# SparkFun_LoRaSerial_433MHz_-_1W.net
KiCad netlist of a schematic drawn in EAGLE
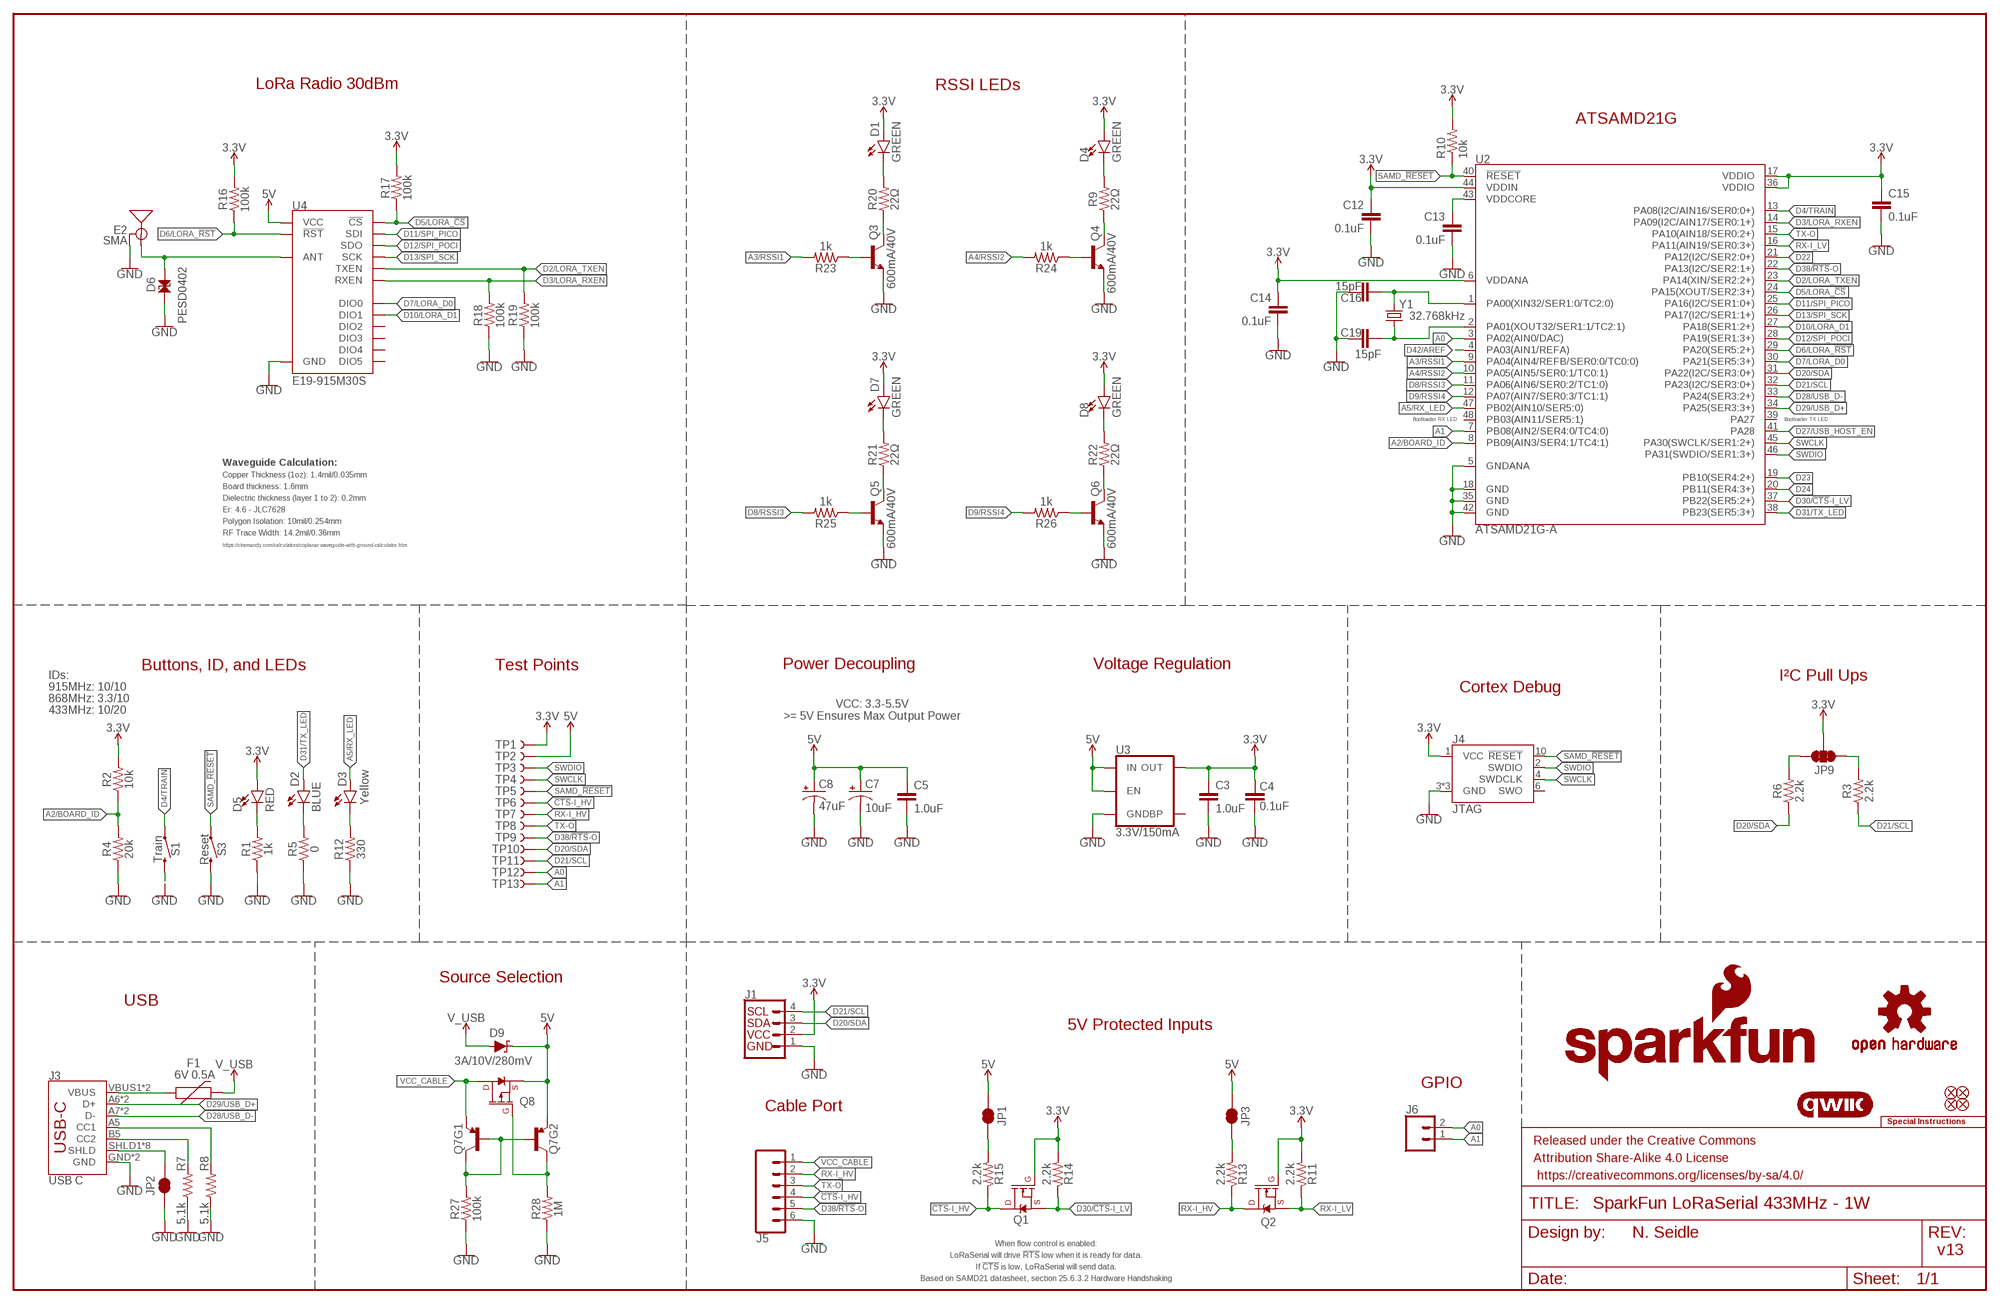
[diagram p0: schematic, sheet 1]

(export (version "E")
  (design (tool "Eeschema 10.0.6"))
  (components
    (comp (ref "C3")
      (value "1.0uF")
      (footprint "eagle-import:0603")
      (libsource (lib "eagle-import") (part "1.0UF-0603-16V-10%-X7R"))
    )
    (comp (ref "C4")
      (value "0.1uF")
      (footprint "eagle-import:0603")
      (libsource (lib "eagle-import") (part "0.1UF-0603-25V-5%"))
    )
    (comp (ref "C5")
      (value "1.0uF")
      (footprint "eagle-import:0603")
      (libsource (lib "eagle-import") (part "1.0UF-0603-16V-10%-X7R"))
    )
    (comp (ref "C7")
      (value "10uF")
      (footprint "eagle-import:EIA3216")
      (libsource (lib "eagle-import") (part "10UF-POLAR-EIA3216-16V-10%(TANT)"))
    )
    (comp (ref "C8")
      (value "47uF")
      (footprint "eagle-import:EIA3528")
      (libsource (lib "eagle-import") (part "47UF-POLAR-EIA3528-10V-10%"))
    )
    (comp (ref "C12")
      (value "0.1uF")
      (footprint "eagle-import:0603")
      (libsource (lib "eagle-import") (part "0.1UF-0603-25V-(+80/-20%)"))
    )
    (comp (ref "C13")
      (value "0.1uF")
      (footprint "eagle-import:0603")
      (libsource (lib "eagle-import") (part "0.1UF-0603-25V-(+80/-20%)"))
    )
    (comp (ref "C14")
      (value "0.1uF")
      (footprint "eagle-import:0603")
      (libsource (lib "eagle-import") (part "0.1UF-0603-25V-(+80/-20%)"))
    )
    (comp (ref "C15")
      (value "0.1uF")
      (footprint "eagle-import:0603")
      (libsource (lib "eagle-import") (part "0.1UF-0603-25V-(+80/-20%)"))
    )
    (comp (ref "C16")
      (value "15pF")
      (footprint "eagle-import:0603")
      (libsource (lib "eagle-import") (part "15PF-0603-50V-5%"))
    )
    (comp (ref "C19")
      (value "15pF")
      (footprint "eagle-import:0603")
      (libsource (lib "eagle-import") (part "15PF-0603-50V-5%"))
    )
    (comp (ref "D1")
      (value "GREEN")
      (footprint "eagle-import:LED-0603")
      (libsource (lib "eagle-import") (part "LED-GREEN0603"))
    )
    (comp (ref "D2")
      (value "BLUE")
      (footprint "eagle-import:LED-0603")
      (libsource (lib "eagle-import") (part "LED-BLUE0603"))
    )
    (comp (ref "D3")
      (value "Yellow")
      (footprint "eagle-import:LED-0603")
      (libsource (lib "eagle-import") (part "LED-YELLOW0603"))
    )
    (comp (ref "D4")
      (value "GREEN")
      (footprint "eagle-import:LED-0603")
      (libsource (lib "eagle-import") (part "LED-GREEN0603"))
    )
    (comp (ref "D5")
      (value "RED")
      (footprint "eagle-import:LED-0603")
      (libsource (lib "eagle-import") (part "LED-RED0603"))
    )
    (comp (ref "D6")
      (value "PESD0402")
      (footprint "eagle-import:0402-TIGHT")
      (libsource (lib "eagle-import") (part "PESD0402-0402T"))
    )
    (comp (ref "D7")
      (value "GREEN")
      (footprint "eagle-import:LED-0603")
      (libsource (lib "eagle-import") (part "LED-GREEN0603"))
    )
    (comp (ref "D8")
      (value "GREEN")
      (footprint "eagle-import:LED-0603")
      (libsource (lib "eagle-import") (part "LED-GREEN0603"))
    )
    (comp (ref "D9")
      (value "3A/10V/280mV")
      (footprint "eagle-import:SOD-323")
      (libsource (lib "eagle-import") (part "DIODE-SCHOTTKY-BAT60A"))
    )
    (comp (ref "E2")
      (value "SMA")
      (footprint "eagle-import:SMA-EDGE")
      (libsource (lib "eagle-import") (part "ANTENNA-SMA-GROUNDEDEDGE_SMA"))
    )
    (comp (ref "F1")
      (value "6V 0.5A")
      (footprint "eagle-import:0805")
      (libsource (lib "eagle-import") (part "PPTC_6V500MA"))
    )
    (comp (ref "FID1")
      (value "FIDUCIAL1X2")
      (footprint "eagle-import:FIDUCIAL-1X2")
      (libsource (lib "eagle-import") (part "FIDUCIAL1X2"))
    )
    (comp (ref "FID2")
      (value "FIDUCIAL1X2")
      (footprint "eagle-import:FIDUCIAL-1X2")
      (libsource (lib "eagle-import") (part "FIDUCIAL1X2"))
    )
    (comp (ref "FID3")
      (value "FIDUCIAL1X2")
      (footprint "eagle-import:FIDUCIAL-1X2")
      (libsource (lib "eagle-import") (part "FIDUCIAL1X2"))
    )
    (comp (ref "FID4")
      (value "FIDUCIAL1X2")
      (footprint "eagle-import:FIDUCIAL-1X2")
      (libsource (lib "eagle-import") (part "FIDUCIAL1X2"))
    )
    (comp (ref "FRAME3")
      (value "FRAME-LEDGER")
      (footprint "eagle-import:CREATIVE_COMMONS")
      (libsource (lib "eagle-import") (part "FRAME-LEDGER"))
    )
    (comp (ref "J1")
      (value "QWIIC_RIGHT_ANGLE")
      (footprint "eagle-import:JST04_1MM_RA")
      (libsource (lib "eagle-import") (part "QWIIC_CONNECTORJS-1MM"))
    )
    (comp (ref "J3")
      (value "USB C")
      (footprint "eagle-import:USB-C-16P")
      (libsource (lib "eagle-import") (part "USB_C16PIN"))
    )
    (comp (ref "J4")
      (value "JTAG")
      (footprint "eagle-import:2X5-PTH-1.27MM-NO_SILK")
      (libsource (lib "eagle-import") (part "CORTEX_JTAG_DEBUG_MINIMUM_PTH_NS"))
    )
    (comp (ref "J5")
      (value "CONN_06JST-SMD-LOCKING")
      (footprint "eagle-import:JST-6-SMD-1.25MM-LOCKING")
      (libsource (lib "eagle-import") (part "CONN_06JST-SMD-LOCKING"))
    )
    (comp (ref "J6")
      (value "CONN_021X02_NO_SILK")
      (footprint "eagle-import:1X02_NO_SILK")
      (libsource (lib "eagle-import") (part "CONN_021X02_NO_SILK"))
    )
    (comp (ref "JP1")
      (value "JUMPER-SMT_2_NC_TRACE_SILK")
      (footprint "eagle-import:SMT-JUMPER_2_NC_TRACE_SILK")
      (libsource (lib "eagle-import") (part "JUMPER-SMT_2_NC_TRACE_SILK"))
    )
    (comp (ref "JP2")
      (value "JUMPER-SMT_2_NC_TRACE_SILK")
      (footprint "eagle-import:SMT-JUMPER_2_NC_TRACE_SILK")
      (libsource (lib "eagle-import") (part "JUMPER-SMT_2_NC_TRACE_SILK"))
    )
    (comp (ref "JP3")
      (value "JUMPER-SMT_2_NC_TRACE_SILK")
      (footprint "eagle-import:SMT-JUMPER_2_NC_TRACE_SILK")
      (libsource (lib "eagle-import") (part "JUMPER-SMT_2_NC_TRACE_SILK"))
    )
    (comp (ref "JP9")
      (value "JUMPER-SMT_3_2-NC_TRACE_SILK")
      (footprint "eagle-import:SMT-JUMPER_3_2-NC_TRACE_SILK")
      (libsource (lib "eagle-import") (part "JUMPER-SMT_3_2-NC_TRACE_SILK"))
    )
    (comp (ref "LOGO1")
      (value "SPECIAL_INSTRUCTIONS-ORDERING")
      (footprint "eagle-import:ORDERING_INSTRUCTIONS")
      (libsource (lib "eagle-import") (part "SPECIAL_INSTRUCTIONS-ORDERING"))
    )
    (comp (ref "LOGO2")
      (value "SFE_LOGO_NAME_FLAME9_MM")
      (footprint "eagle-import:SFE_LOGO_NAME_FLAME_9MM")
      (libsource (lib "eagle-import") (part "SFE_LOGO_NAME_FLAME9_MM"))
    )
    (comp (ref "LOGO3")
      (value "QWIIC_LOGO_CONNECTOR")
      (footprint "eagle-import:QWIIC_5.5MM")
      (libsource (lib "eagle-import") (part "QWIIC_LOGO_CONNECTOR"))
    )
    (comp (ref "LOGO4")
      (value "OSHW-LOGOMINI")
      (footprint "eagle-import:OSHW-LOGO-MINI")
      (libsource (lib "eagle-import") (part "OSHW-LOGOMINI"))
    )
    (comp (ref "LOGO5")
      (value "SFE_LOGO_NAME9_MM")
      (footprint "eagle-import:SFE_LOGO_NAME_9MM")
      (libsource (lib "eagle-import") (part "SFE_LOGO_NAME9_MM"))
    )
    (comp (ref "Q1")
      (value "20V/0.2A/8MHz/1.2Ω/1Vth")
      (footprint "eagle-import:SOT-416FL")
      (libsource (lib "eagle-import") (part "MOSFET-NCH-RE1C002UNTCL"))
    )
    (comp (ref "Q2")
      (value "20V/0.2A/8MHz/1.2Ω/1Vth")
      (footprint "eagle-import:SOT-416FL")
      (libsource (lib "eagle-import") (part "MOSFET-NCH-RE1C002UNTCL"))
    )
    (comp (ref "Q3")
      (value "600mA/40V")
      (footprint "eagle-import:SOT23-3")
      (libsource (lib "eagle-import") (part "TRANS_NPN-MMBT2222AL"))
    )
    (comp (ref "Q4")
      (value "600mA/40V")
      (footprint "eagle-import:SOT23-3")
      (libsource (lib "eagle-import") (part "TRANS_NPN-MMBT2222AL"))
    )
    (comp (ref "Q5")
      (value "600mA/40V")
      (footprint "eagle-import:SOT23-3")
      (libsource (lib "eagle-import") (part "TRANS_NPN-MMBT2222AL"))
    )
    (comp (ref "Q6")
      (value "600mA/40V")
      (footprint "eagle-import:SOT23-3")
      (libsource (lib "eagle-import") (part "TRANS_NPN-MMBT2222AL"))
    )
    (comp (ref "Q7")
      (value "TRANS_PNP_DUALSOT-363")
      (footprint "eagle-import:SOT363_PHILIPS")
      (libsource (lib "eagle-import") (part "TRANS_PNP_DUALSOT-363"))
    )
    (comp (ref "Q8")
      (value "20V/4.2A/52mΩ/1.4W")
      (footprint "eagle-import:SOT23-3")
      (libsource (lib "eagle-import") (part "MOSFET_PCH-DMG2305UX-7"))
    )
    (comp (ref "R1")
      (value "1k")
      (footprint "eagle-import:0603")
      (libsource (lib "eagle-import") (part "1KOHM-0603-1/10W-1%"))
    )
    (comp (ref "R2")
      (value "10k")
      (footprint "eagle-import:0603")
      (libsource (lib "eagle-import") (part "10KOHM-0603-1/10W-1%"))
    )
    (comp (ref "R3")
      (value "2.2k")
      (footprint "eagle-import:0603")
      (libsource (lib "eagle-import") (part "2.2KOHM-0603-1/10W-1%"))
    )
    (comp (ref "R4")
      (value "20k")
      (footprint "eagle-import:0603")
      (libsource (lib "eagle-import") (part "20KOHM-0603-1/10W-1%"))
    )
    (comp (ref "R5")
      (value "0")
      (footprint "eagle-import:0603")
      (libsource (lib "eagle-import") (part "0OHM-0603-1/10W"))
    )
    (comp (ref "R6")
      (value "2.2k")
      (footprint "eagle-import:0603")
      (libsource (lib "eagle-import") (part "2.2KOHM-0603-1/10W-1%"))
    )
    (comp (ref "R7")
      (value "5.1k")
      (footprint "eagle-import:0603")
      (libsource (lib "eagle-import") (part "5.1KOHM5.1KOHM-0603-1/10W-1%"))
    )
    (comp (ref "R8")
      (value "5.1k")
      (footprint "eagle-import:0603")
      (libsource (lib "eagle-import") (part "5.1KOHM5.1KOHM-0603-1/10W-1%"))
    )
    (comp (ref "R9")
      (value "22Ω")
      (footprint "eagle-import:0603")
      (libsource (lib "eagle-import") (part "22OHM-0603-1/10W-1%"))
    )
    (comp (ref "R10")
      (value "10k")
      (footprint "eagle-import:0603")
      (libsource (lib "eagle-import") (part "10KOHM-0603-1/10W-1%"))
    )
    (comp (ref "R11")
      (value "2.2k")
      (footprint "eagle-import:0603")
      (libsource (lib "eagle-import") (part "2.2KOHM-0603-1/10W-1%"))
    )
    (comp (ref "R12")
      (value "330")
      (footprint "eagle-import:0603")
      (libsource (lib "eagle-import") (part "330OHM-0603-1/10W-1%"))
    )
    (comp (ref "R13")
      (value "2.2k")
      (footprint "eagle-import:0603")
      (libsource (lib "eagle-import") (part "2.2KOHM-0603-1/10W-1%"))
    )
    (comp (ref "R14")
      (value "2.2k")
      (footprint "eagle-import:0603")
      (libsource (lib "eagle-import") (part "2.2KOHM-0603-1/10W-1%"))
    )
    (comp (ref "R15")
      (value "2.2k")
      (footprint "eagle-import:0603")
      (libsource (lib "eagle-import") (part "2.2KOHM-0603-1/10W-1%"))
    )
    (comp (ref "R16")
      (value "100k")
      (footprint "eagle-import:0603")
      (libsource (lib "eagle-import") (part "100KOHM-0603-1/10W-1%"))
    )
    (comp (ref "R17")
      (value "100k")
      (footprint "eagle-import:0603")
      (libsource (lib "eagle-import") (part "100KOHM-0603-1/10W-1%"))
    )
    (comp (ref "R18")
      (value "100k")
      (footprint "eagle-import:0603")
      (libsource (lib "eagle-import") (part "100KOHM-0603-1/10W-1%"))
    )
    (comp (ref "R19")
      (value "100k")
      (footprint "eagle-import:0603")
      (libsource (lib "eagle-import") (part "100KOHM-0603-1/10W-1%"))
    )
    (comp (ref "R20")
      (value "22Ω")
      (footprint "eagle-import:0603")
      (libsource (lib "eagle-import") (part "22OHM-0603-1/10W-1%"))
    )
    (comp (ref "R21")
      (value "22Ω")
      (footprint "eagle-import:0603")
      (libsource (lib "eagle-import") (part "22OHM-0603-1/10W-1%"))
    )
    (comp (ref "R22")
      (value "22Ω")
      (footprint "eagle-import:0603")
      (libsource (lib "eagle-import") (part "22OHM-0603-1/10W-1%"))
    )
    (comp (ref "R23")
      (value "1k")
      (footprint "eagle-import:0603")
      (libsource (lib "eagle-import") (part "1KOHM-0603-1/10W-1%"))
    )
    (comp (ref "R24")
      (value "1k")
      (footprint "eagle-import:0603")
      (libsource (lib "eagle-import") (part "1KOHM-0603-1/10W-1%"))
    )
    (comp (ref "R25")
      (value "1k")
      (footprint "eagle-import:0603")
      (libsource (lib "eagle-import") (part "1KOHM-0603-1/10W-1%"))
    )
    (comp (ref "R26")
      (value "1k")
      (footprint "eagle-import:0603")
      (libsource (lib "eagle-import") (part "1KOHM-0603-1/10W-1%"))
    )
    (comp (ref "R27")
      (value "100k")
      (footprint "eagle-import:0603")
      (libsource (lib "eagle-import") (part "100KOHM-0603-1/10W-1%"))
    )
    (comp (ref "R28")
      (value "1M")
      (footprint "eagle-import:0603")
      (libsource (lib "eagle-import") (part "1MOHM-0603-1/4W-5%"))
    )
    (comp (ref "S1")
      (value "Train")
      (footprint "eagle-import:TACTILE_SWITCH_SMD_RIGHT_ANGLE")
      (libsource (lib "eagle-import") (part "MOMENTARY-SWITCH-SPST-SMD-RIGHT-ANGLE"))
    )
    (comp (ref "S3")
      (value "Reset")
      (footprint "eagle-import:TACTILE_SWITCH_SMD_5.2MM")
      (libsource (lib "eagle-import") (part "MOMENTARY-SWITCH-SPST-SMD-5.2-TALL-REDUNDANT"))
    )
    (comp (ref "TP1")
      (value "TEST-POINT3X5")
      (footprint "eagle-import:PAD.03X.05")
      (libsource (lib "eagle-import") (part "TEST-POINT3X5"))
    )
    (comp (ref "TP2")
      (value "TEST-POINT3X5")
      (footprint "eagle-import:PAD.03X.05")
      (libsource (lib "eagle-import") (part "TEST-POINT3X5"))
    )
    (comp (ref "TP3")
      (value "TEST-POINT3X5")
      (footprint "eagle-import:PAD.03X.05")
      (libsource (lib "eagle-import") (part "TEST-POINT3X5"))
    )
    (comp (ref "TP4")
      (value "TEST-POINT3X5")
      (footprint "eagle-import:PAD.03X.05")
      (libsource (lib "eagle-import") (part "TEST-POINT3X5"))
    )
    (comp (ref "TP5")
      (value "TEST-POINT3X5")
      (footprint "eagle-import:PAD.03X.05")
      (libsource (lib "eagle-import") (part "TEST-POINT3X5"))
    )
    (comp (ref "TP6")
      (value "TEST-POINT3X5")
      (footprint "eagle-import:PAD.03X.05")
      (libsource (lib "eagle-import") (part "TEST-POINT3X5"))
    )
    (comp (ref "TP7")
      (value "TEST-POINT3X5")
      (footprint "eagle-import:PAD.03X.05")
      (libsource (lib "eagle-import") (part "TEST-POINT3X5"))
    )
    (comp (ref "TP8")
      (value "TEST-POINT3X5")
      (footprint "eagle-import:PAD.03X.05")
      (libsource (lib "eagle-import") (part "TEST-POINT3X5"))
    )
    (comp (ref "TP9")
      (value "TEST-POINT3X5")
      (footprint "eagle-import:PAD.03X.05")
      (libsource (lib "eagle-import") (part "TEST-POINT3X5"))
    )
    (comp (ref "TP10")
      (value "TEST-POINT3X5")
      (footprint "eagle-import:PAD.03X.05")
      (libsource (lib "eagle-import") (part "TEST-POINT3X5"))
    )
    (comp (ref "TP11")
      (value "TEST-POINT3X5")
      (footprint "eagle-import:PAD.03X.05")
      (libsource (lib "eagle-import") (part "TEST-POINT3X5"))
    )
    (comp (ref "TP12")
      (value "TEST-POINT3X5")
      (footprint "eagle-import:PAD.03X.05")
      (libsource (lib "eagle-import") (part "TEST-POINT3X5"))
    )
    (comp (ref "TP13")
      (value "TEST-POINT3X5")
      (footprint "eagle-import:PAD.03X.05")
      (libsource (lib "eagle-import") (part "TEST-POINT3X5"))
    )
    (comp (ref "U2")
      (value "ATSAMD21G-A")
      (footprint "eagle-import:TQFP-48")
      (libsource (lib "eagle-import") (part "ATSAMD21G-A"))
    )
    (comp (ref "U3")
      (value "3.3V/150mA")
      (footprint "eagle-import:SOT23-5")
      (libsource (lib "eagle-import") (part "V_REG_MIC52053.3V"))
    )
    (comp (ref "U4")
      (value "E19-915M30S")
      (footprint "eagle-import:E19-433M30S")
      (libsource (lib "eagle-import") (part "LORA-E19433MHZ"))
    )
    (comp (ref "Y1")
      (value "32.768kHz")
      (footprint "eagle-import:CRYSTAL-SMD-3.2X1.5MM")
      (libsource (lib "eagle-import") (part "CRYSTAL3.2X1.5MM"))
    )
  )
  (nets
    (net (code "1") (name "/D5{slash}LORA_~{CS}") (class "Default")
      (node (ref "R17") (pin "1") (pinfunction "1_1") (pintype "passive"))
      (node (ref "U2") (pin "24") (pinfunction "PA15(XOUT/SER2:3+)_24") (pintype "bidirectional"))
      (node (ref "U4") (pin "15") (pinfunction "~{CS}_15") (pintype "bidirectional"))
    )
    (net (code "2") (name "/D6{slash}LORA_~{RST}") (class "Default")
      (node (ref "R16") (pin "1") (pinfunction "1_1") (pintype "passive"))
      (node (ref "U2") (pin "29") (pinfunction "PA20(SER5:2+)_29") (pintype "bidirectional"))
      (node (ref "U4") (pin "8") (pinfunction "~{RST}_8") (pintype "bidirectional"))
    )
    (net (code "3") (name "/D30{slash}~{CTS}-I_LV") (class "Default")
      (node (ref "Q1") (pin "2") (pinfunction "S_2") (pintype "bidirectional"))
      (node (ref "R14") (pin "1") (pinfunction "1_1") (pintype "passive"))
      (node (ref "U2") (pin "37") (pinfunction "PB22(SER5:2+)_37") (pintype "bidirectional"))
    )
    (net (code "4") (name "/D38{slash}~{RTS}-O") (class "Default")
      (node (ref "J5") (pin "5") (pinfunction "5_5") (pintype "passive"))
      (node (ref "TP9") (pin "1") (pinfunction "1_1") (pintype "bidirectional"))
      (node (ref "U2") (pin "22") (pinfunction "PA13(I2C/SER2:1+)_22") (pintype "bidirectional"))
    )
    (net (code "5") (name "/SAMD_~{RESET}") (class "Default")
      (node (ref "J4") (pin "10") (pinfunction "~{RESET}_10") (pintype "bidirectional"))
      (node (ref "R10") (pin "1") (pinfunction "1_1") (pintype "passive"))
      (node (ref "S3") (pin "1") (pinfunction "1_1") (pintype "passive"))
      (node (ref "S3") (pin "2") (pinfunction "1_2") (pintype "passive"))
      (node (ref "TP5") (pin "1") (pinfunction "1_1") (pintype "bidirectional"))
      (node (ref "U2") (pin "40") (pinfunction "~{RESET}_40") (pintype "bidirectional"))
    )
    (net (code "6") (name "/~{CTS}-I_HV") (class "Default")
      (node (ref "J5") (pin "4") (pinfunction "4_4") (pintype "passive"))
      (node (ref "Q1") (pin "3") (pinfunction "D_3") (pintype "bidirectional"))
      (node (ref "R15") (pin "1") (pinfunction "1_1") (pintype "passive"))
      (node (ref "TP6") (pin "1") (pinfunction "1_1") (pintype "bidirectional"))
    )
    (net (code "7") (name "3.3V") (class "Default")
      (node (ref "C12") (pin "1") (pinfunction "1_1") (pintype "passive"))
      (node (ref "C14") (pin "1") (pinfunction "1_1") (pintype "passive"))
      (node (ref "C15") (pin "1") (pinfunction "1_1") (pintype "passive"))
      (node (ref "C3") (pin "1") (pinfunction "1_1") (pintype "passive"))
      (node (ref "C4") (pin "2") (pinfunction "2_2") (pintype "passive"))
      (node (ref "D1") (pin "A") (pinfunction "A_A") (pintype "passive"))
      (node (ref "D4") (pin "A") (pinfunction "A_A") (pintype "passive"))
      (node (ref "D5") (pin "A") (pinfunction "A_A") (pintype "passive"))
      (node (ref "D7") (pin "A") (pinfunction "A_A") (pintype "passive"))
      (node (ref "D8") (pin "A") (pinfunction "A_A") (pintype "passive"))
      (node (ref "J1") (pin "2") (pinfunction "2_2") (pintype "power_in"))
      (node (ref "J4") (pin "1") (pinfunction "VCC_1") (pintype "bidirectional"))
      (node (ref "JP9") (pin "2") (pinfunction "2_2") (pintype "passive"))
      (node (ref "Q1") (pin "1") (pinfunction "G_1") (pintype "bidirectional"))
      (node (ref "Q2") (pin "1") (pinfunction "G_1") (pintype "bidirectional"))
      (node (ref "R10") (pin "2") (pinfunction "2_2") (pintype "passive"))
      (node (ref "R11") (pin "2") (pinfunction "2_2") (pintype "passive"))
      (node (ref "R14") (pin "2") (pinfunction "2_2") (pintype "passive"))
      (node (ref "R16") (pin "2") (pinfunction "2_2") (pintype "passive"))
      (node (ref "R17") (pin "2") (pinfunction "2_2") (pintype "passive"))
      (node (ref "R2") (pin "2") (pinfunction "2_2") (pintype "passive"))
      (node (ref "TP1") (pin "1") (pinfunction "1_1") (pintype "bidirectional"))
      (node (ref "U2") (pin "17") (pinfunction "VDDIO_17") (pintype "bidirectional"))
      (node (ref "U2") (pin "36") (pinfunction "VDDIO_36") (pintype "bidirectional"))
      (node (ref "U2") (pin "44") (pinfunction "VDDIN_44") (pintype "bidirectional"))
      (node (ref "U2") (pin "6") (pinfunction "VDDANA_6") (pintype "bidirectional"))
      (node (ref "U3") (pin "5") (pinfunction "OUT_5") (pintype "passive"))
    )
    (net (code "8") (name "5V") (class "Default")
      (node (ref "C5") (pin "1") (pinfunction "1_1") (pintype "passive"))
      (node (ref "C7") (pin "+") (pinfunction "+_+") (pintype "passive"))
      (node (ref "C8") (pin "A") (pinfunction "+_A") (pintype "passive"))
      (node (ref "D9") (pin "C") (pinfunction "C_C") (pintype "passive"))
      (node (ref "JP1") (pin "2") (pinfunction "2_2") (pintype "passive"))
      (node (ref "JP3") (pin "2") (pinfunction "2_2") (pintype "passive"))
      (node (ref "Q7") (pin "4") (pinfunction "E_4") (pintype "passive"))
      (node (ref "Q8") (pin "2") (pinfunction "S_2") (pintype "bidirectional"))
      (node (ref "TP2") (pin "1") (pinfunction "1_1") (pintype "bidirectional"))
      (node (ref "U3") (pin "1") (pinfunction "IN_1") (pintype "input"))
      (node (ref "U3") (pin "3") (pinfunction "EN_3") (pintype "input"))
      (node (ref "U4") (pin "11") (pinfunction "VCC_11") (pintype "bidirectional"))
    )
    (net (code "9") (name "A0") (class "Default")
      (node (ref "J6") (pin "2") (pinfunction "2_2") (pintype "passive"))
      (node (ref "TP12") (pin "1") (pinfunction "1_1") (pintype "bidirectional"))
      (node (ref "U2") (pin "3") (pinfunction "PA02(AIN0/DAC)_3") (pintype "bidirectional"))
    )
    (net (code "10") (name "A1") (class "Default")
      (node (ref "J6") (pin "1") (pinfunction "1_1") (pintype "passive"))
      (node (ref "TP13") (pin "1") (pinfunction "1_1") (pintype "bidirectional"))
      (node (ref "U2") (pin "7") (pinfunction "PB08(AIN2/SER4:0/TC4:0)_7") (pintype "bidirectional"))
    )
    (net (code "11") (name "A2{slash}BOARD_ID") (class "Default")
      (node (ref "R2") (pin "1") (pinfunction "1_1") (pintype "passive"))
      (node (ref "R4") (pin "2") (pinfunction "2_2") (pintype "passive"))
      (node (ref "U2") (pin "8") (pinfunction "PB09(AIN3/SER4:1/TC4:1)_8") (pintype "bidirectional"))
    )
    (net (code "12") (name "A3{slash}RSSI1") (class "Default")
      (node (ref "R23") (pin "2") (pinfunction "2_2") (pintype "passive"))
      (node (ref "U2") (pin "9") (pinfunction "PA04(AIN4/REFB/SER0:0/TC0:0)_9") (pintype "bidirectional"))
    )
    (net (code "13") (name "A4{slash}RSSI2") (class "Default")
      (node (ref "R24") (pin "2") (pinfunction "2_2") (pintype "passive"))
      (node (ref "U2") (pin "10") (pinfunction "PA05(AIN5/SER0:1/TC0:1)_10") (pintype "bidirectional"))
    )
    (net (code "14") (name "A5{slash}RX_LED") (class "Default")
      (node (ref "D3") (pin "A") (pinfunction "A_A") (pintype "passive"))
      (node (ref "U2") (pin "47") (pinfunction "PB02(AIN10/SER5:0)_47") (pintype "bidirectional"))
    )
    (net (code "15") (name "D2{slash}LORA_TXEN") (class "Default")
      (node (ref "R19") (pin "2") (pinfunction "2_2") (pintype "passive"))
      (node (ref "U2") (pin "23") (pinfunction "PA14(XIN/SER2:2+)_23") (pintype "bidirectional"))
      (node (ref "U4") (pin "16") (pinfunction "TXEN_16") (pintype "bidirectional"))
    )
    (net (code "16") (name "D3{slash}LORA_RXEN") (class "Default")
      (node (ref "R18") (pin "2") (pinfunction "2_2") (pintype "passive"))
      (node (ref "U2") (pin "14") (pinfunction "PA09(I2C/AIN17/SER0:1+)_14") (pintype "bidirectional"))
      (node (ref "U4") (pin "17") (pinfunction "RXEN_17") (pintype "bidirectional"))
    )
    (net (code "17") (name "D4{slash}TRAIN") (class "Default")
      (node (ref "S1") (pin "1") (pinfunction "1_1") (pintype "passive"))
      (node (ref "U2") (pin "13") (pinfunction "PA08(I2C/AIN16/SER0:0+)_13") (pintype "bidirectional"))
    )
    (net (code "18") (name "D7{slash}LORA_D0") (class "Default")
      (node (ref "U2") (pin "30") (pinfunction "PA21(SER5:3+)_30") (pintype "bidirectional"))
      (node (ref "U4") (pin "7") (pinfunction "DIO0_7") (pintype "bidirectional"))
    )
    (net (code "19") (name "D8{slash}RSSI3") (class "Default")
      (node (ref "R25") (pin "2") (pinfunction "2_2") (pintype "passive"))
      (node (ref "U2") (pin "11") (pinfunction "PA06(AIN6/SER0:2/TC1:0)_11") (pintype "bidirectional"))
    )
    (net (code "20") (name "D9{slash}RSSI4") (class "Default")
      (node (ref "R26") (pin "2") (pinfunction "2_2") (pintype "passive"))
      (node (ref "U2") (pin "12") (pinfunction "PA07(AIN7/SER0:3/TC1:1)_12") (pintype "bidirectional"))
    )
    (net (code "21") (name "D10{slash}LORA_D1") (class "Default")
      (node (ref "U2") (pin "27") (pinfunction "PA18(SER1:2+)_27") (pintype "bidirectional"))
      (node (ref "U4") (pin "6") (pinfunction "DIO1_6") (pintype "bidirectional"))
    )
    (net (code "22") (name "D11{slash}SPI_PICO") (class "Default")
      (node (ref "U2") (pin "25") (pinfunction "PA16(I2C/SER1:0+)_25") (pintype "bidirectional"))
      (node (ref "U4") (pin "14") (pinfunction "SDI_14") (pintype "bidirectional"))
    )
    (net (code "23") (name "D12{slash}SPI_POCI") (class "Default")
      (node (ref "U2") (pin "28") (pinfunction "PA19(SER1:3+)_28") (pintype "bidirectional"))
      (node (ref "U4") (pin "13") (pinfunction "SDO_13") (pintype "bidirectional"))
    )
    (net (code "24") (name "D13{slash}SPI_SCK") (class "Default")
      (node (ref "U2") (pin "26") (pinfunction "PA17(I2C/SER1:1+)_26") (pintype "bidirectional"))
      (node (ref "U4") (pin "12") (pinfunction "SCK_12") (pintype "bidirectional"))
    )
    (net (code "25") (name "D20{slash}SDA") (class "Default")
      (node (ref "J1") (pin "3") (pinfunction "3_3") (pintype "passive"))
      (node (ref "R6") (pin "1") (pinfunction "1_1") (pintype "passive"))
      (node (ref "TP10") (pin "1") (pinfunction "1_1") (pintype "bidirectional"))
      (node (ref "U2") (pin "31") (pinfunction "PA22(I2C/SER3:0+)_31") (pintype "bidirectional"))
    )
    (net (code "26") (name "D21{slash}SCL") (class "Default")
      (node (ref "J1") (pin "4") (pinfunction "4_4") (pintype "passive"))
      (node (ref "R3") (pin "1") (pinfunction "1_1") (pintype "passive"))
      (node (ref "TP11") (pin "1") (pinfunction "1_1") (pintype "bidirectional"))
      (node (ref "U2") (pin "32") (pinfunction "PA23(I2C/SER3:0+)_32") (pintype "bidirectional"))
    )
    (net (code "27") (name "D22") (class "Default")
      (node (ref "U2") (pin "21") (pinfunction "PA12(I2C/SER2:0+)_21") (pintype "bidirectional"))
    )
    (net (code "28") (name "D23") (class "Default")
      (node (ref "U2") (pin "19") (pinfunction "PB10(SER4:2+)_19") (pintype "bidirectional"))
    )
    (net (code "29") (name "D24") (class "Default")
      (node (ref "U2") (pin "20") (pinfunction "PB11(SER4:3+)_20") (pintype "bidirectional"))
    )
    (net (code "30") (name "D27{slash}USB_HOST_EN") (class "Default")
      (node (ref "U2") (pin "41") (pinfunction "PA28_41") (pintype "bidirectional"))
    )
    (net (code "31") (name "D28{slash}USB_D-") (class "Default")
      (node (ref "J3") (pin "A7") (pinfunction "D-_A7") (pintype "bidirectional"))
      (node (ref "J3") (pin "B7") (pinfunction "D-_B7") (pintype "bidirectional"))
      (node (ref "U2") (pin "33") (pinfunction "PA24(SER3:2+)_33") (pintype "bidirectional"))
    )
    (net (code "32") (name "D29{slash}USB_D+") (class "Default")
      (node (ref "J3") (pin "A6") (pinfunction "D+_A6") (pintype "bidirectional"))
      (node (ref "J3") (pin "B6") (pinfunction "D+_B6") (pintype "bidirectional"))
      (node (ref "U2") (pin "34") (pinfunction "PA25(SER3:3+)_34") (pintype "bidirectional"))
    )
    (net (code "33") (name "D31{slash}TX_LED") (class "Default")
      (node (ref "D2") (pin "A") (pinfunction "A_A") (pintype "passive"))
      (node (ref "U2") (pin "38") (pinfunction "PB23(SER5:3+)_38") (pintype "bidirectional"))
    )
    (net (code "34") (name "D42{slash}AREF") (class "Default")
      (node (ref "U2") (pin "4") (pinfunction "PA03(AIN1/REFA)_4") (pintype "bidirectional"))
    )
    (net (code "35") (name "GND") (class "Default")
      (node (ref "C12") (pin "2") (pinfunction "2_2") (pintype "passive"))
      (node (ref "C13") (pin "2") (pinfunction "2_2") (pintype "passive"))
      (node (ref "C14") (pin "2") (pinfunction "2_2") (pintype "passive"))
      (node (ref "C15") (pin "2") (pinfunction "2_2") (pintype "passive"))
      (node (ref "C16") (pin "1") (pinfunction "1_1") (pintype "passive"))
      (node (ref "C19") (pin "2") (pinfunction "2_2") (pintype "passive"))
      (node (ref "C3") (pin "2") (pinfunction "2_2") (pintype "passive"))
      (node (ref "C4") (pin "1") (pinfunction "1_1") (pintype "passive"))
      (node (ref "C5") (pin "2") (pinfunction "2_2") (pintype "passive"))
      (node (ref "C7") (pin "-") (pinfunction "-_-") (pintype "passive"))
      (node (ref "C8") (pin "C") (pinfunction "-_C") (pintype "passive"))
      (node (ref "D6") (pin "1") (pinfunction "1_1") (pintype "bidirectional"))
      (node (ref "E2") (pin "GND@0") (pinfunction "GND_GND@0") (pintype "bidirectional"))
      (node (ref "E2") (pin "GND@1") (pinfunction "GND_GND@1") (pintype "bidirectional"))
      (node (ref "E2") (pin "GND@2") (pinfunction "GND_GND@2") (pintype "bidirectional"))
      (node (ref "E2") (pin "GND@3") (pinfunction "GND_GND@3") (pintype "bidirectional"))
      (node (ref "J1") (pin "1") (pinfunction "1_1") (pintype "power_in"))
      (node (ref "J3") (pin "GND") (pinfunction "GND_GND") (pintype "bidirectional"))
      (node (ref "J3") (pin "GND2") (pinfunction "GND_GND2") (pintype "bidirectional"))
      (node (ref "J4") (pin "3") (pinfunction "GND_3") (pintype "bidirectional"))
      (node (ref "J4") (pin "5") (pinfunction "GND_5") (pintype "bidirectional"))
      (node (ref "J4") (pin "9") (pinfunction "GND_9") (pintype "bidirectional"))
      (node (ref "J5") (pin "6") (pinfunction "6_6") (pintype "passive"))
      (node (ref "JP2") (pin "1") (pinfunction "1_1") (pintype "passive"))
      (node (ref "Q3") (pin "2") (pinfunction "E_2") (pintype "passive"))
      (node (ref "Q4") (pin "2") (pinfunction "E_2") (pintype "passive"))
      (node (ref "Q5") (pin "2") (pinfunction "E_2") (pintype "passive"))
      (node (ref "Q6") (pin "2") (pinfunction "E_2") (pintype "passive"))
      (node (ref "R1") (pin "1") (pinfunction "1_1") (pintype "passive"))
      (node (ref "R12") (pin "1") (pinfunction "1_1") (pintype "passive"))
      (node (ref "R18") (pin "1") (pinfunction "1_1") (pintype "passive"))
      (node (ref "R19") (pin "1") (pinfunction "1_1") (pintype "passive"))
      (node (ref "R27") (pin "1") (pinfunction "1_1") (pintype "passive"))
      (node (ref "R28") (pin "1") (pinfunction "1_1") (pintype "passive"))
      (node (ref "R4") (pin "1") (pinfunction "1_1") (pintype "passive"))
      (node (ref "R5") (pin "1") (pinfunction "1_1") (pintype "passive"))
      (node (ref "R7") (pin "1") (pinfunction "1_1") (pintype "passive"))
      (node (ref "R8") (pin "1") (pinfunction "1_1") (pintype "passive"))
      (node (ref "S1") (pin "2") (pinfunction "2_2") (pintype "passive"))
      (node (ref "S3") (pin "3") (pinfunction "2_3") (pintype "passive"))
      (node (ref "S3") (pin "4") (pinfunction "2_4") (pintype "passive"))
      (node (ref "U2") (pin "18") (pinfunction "GND_18") (pintype "bidirectional"))
      (node (ref "U2") (pin "35") (pinfunction "GND_35") (pintype "bidirectional"))
      (node (ref "U2") (pin "42") (pinfunction "GND_42") (pintype "bidirectional"))
      (node (ref "U2") (pin "5") (pinfunction "GNDANA_5") (pintype "bidirectional"))
      (node (ref "U3") (pin "2") (pinfunction "GND_2") (pintype "input"))
      (node (ref "U4") (pin "1") (pinfunction "GND_1") (pintype "bidirectional"))
      (node (ref "U4") (pin "10") (pinfunction "GND_10") (pintype "bidirectional"))
      (node (ref "U4") (pin "18") (pinfunction "GND_18") (pintype "bidirectional"))
      (node (ref "U4") (pin "20") (pinfunction "GND_20") (pintype "bidirectional"))
      (node (ref "U4") (pin "21") (pinfunction "GND_21") (pintype "bidirectional"))
      (node (ref "U4") (pin "22") (pinfunction "GND_22") (pintype "bidirectional"))
      (node (ref "U4") (pin "9") (pinfunction "GND_9") (pintype "bidirectional"))
    )
    (net (code "36") (name "Net-(D1-PadC)") (class "Default")
      (node (ref "D1") (pin "C") (pinfunction "C_C") (pintype "passive"))
      (node (ref "R20") (pin "2") (pinfunction "2_2") (pintype "passive"))
    )
    (net (code "37") (name "Net-(D2-PadC)") (class "Default")
      (node (ref "D2") (pin "C") (pinfunction "C_C") (pintype "passive"))
      (node (ref "R5") (pin "2") (pinfunction "2_2") (pintype "passive"))
    )
    (net (code "38") (name "Net-(D3-PadC)") (class "Default")
      (node (ref "D3") (pin "C") (pinfunction "C_C") (pintype "passive"))
      (node (ref "R12") (pin "2") (pinfunction "2_2") (pintype "passive"))
    )
    (net (code "39") (name "Net-(D4-PadC)") (class "Default")
      (node (ref "D4") (pin "C") (pinfunction "C_C") (pintype "passive"))
      (node (ref "R9") (pin "2") (pinfunction "2_2") (pintype "passive"))
    )
    (net (code "40") (name "Net-(D5-PadC)") (class "Default")
      (node (ref "D5") (pin "C") (pinfunction "C_C") (pintype "passive"))
      (node (ref "R1") (pin "2") (pinfunction "2_2") (pintype "passive"))
    )
    (net (code "41") (name "Net-(D7-PadC)") (class "Default")
      (node (ref "D7") (pin "C") (pinfunction "C_C") (pintype "passive"))
      (node (ref "R21") (pin "2") (pinfunction "2_2") (pintype "passive"))
    )
    (net (code "42") (name "Net-(D8-PadC)") (class "Default")
      (node (ref "D8") (pin "C") (pinfunction "C_C") (pintype "passive"))
      (node (ref "R22") (pin "2") (pinfunction "2_2") (pintype "passive"))
    )
    (net (code "43") (name "Net-(E2-SIGNAL)") (class "Default")
      (node (ref "D6") (pin "2") (pinfunction "2_2") (pintype "bidirectional"))
      (node (ref "E2") (pin "SIG") (pinfunction "SIGNAL_SIG") (pintype "bidirectional"))
      (node (ref "U4") (pin "19") (pinfunction "ANT_19") (pintype "bidirectional"))
    )
    (net (code "44") (name "Net-(F1-Pad1)") (class "Default")
      (node (ref "F1") (pin "1") (pinfunction "1_1") (pintype "bidirectional"))
      (node (ref "J3") (pin "VBUS1") (pinfunction "VBUS_VBUS1") (pintype "bidirectional"))
      (node (ref "J3") (pin "VBUS2") (pinfunction "VBUS_VBUS2") (pintype "bidirectional"))
    )
    (net (code "45") (name "Net-(J3-CC1)") (class "Default")
      (node (ref "J3") (pin "A5") (pinfunction "CC1_A5") (pintype "bidirectional"))
      (node (ref "R8") (pin "2") (pinfunction "2_2") (pintype "passive"))
    )
    (net (code "46") (name "Net-(J3-CC2)") (class "Default")
      (node (ref "J3") (pin "B5") (pinfunction "CC2_B5") (pintype "bidirectional"))
      (node (ref "R7") (pin "2") (pinfunction "2_2") (pintype "passive"))
    )
    (net (code "47") (name "Net-(J3-SHLD-PadSHLD1)") (class "Default")
      (node (ref "J3") (pin "SHLD1") (pinfunction "SHLD_SHLD1") (pintype "bidirectional"))
      (node (ref "J3") (pin "SHLD2") (pinfunction "SHLD_SHLD2") (pintype "bidirectional"))
      (node (ref "J3") (pin "SHLD3") (pinfunction "SHLD_SHLD3") (pintype "bidirectional"))
      (node (ref "J3") (pin "SHLD4") (pinfunction "SHLD_SHLD4") (pintype "bidirectional"))
      (node (ref "J3") (pin "SHLD5") (pinfunction "SHLD_SHLD5") (pintype "bidirectional"))
      (node (ref "J3") (pin "SHLD6") (pinfunction "SHLD_SHLD6") (pintype "bidirectional"))
      (node (ref "J3") (pin "SHLD7") (pinfunction "SHLD_SHLD7") (pintype "bidirectional"))
      (node (ref "J3") (pin "SHLD8") (pinfunction "SHLD_SHLD8") (pintype "bidirectional"))
      (node (ref "JP2") (pin "2") (pinfunction "2_2") (pintype "passive"))
    )
    (net (code "48") (name "Net-(JP1-Pad1)") (class "Default")
      (node (ref "JP1") (pin "1") (pinfunction "1_1") (pintype "passive"))
      (node (ref "R15") (pin "2") (pinfunction "2_2") (pintype "passive"))
    )
    (net (code "49") (name "Net-(JP3-Pad1)") (class "Default")
      (node (ref "JP3") (pin "1") (pinfunction "1_1") (pintype "passive"))
      (node (ref "R13") (pin "2") (pinfunction "2_2") (pintype "passive"))
    )
    (net (code "50") (name "Net-(JP9-Pad1)") (class "Default")
      (node (ref "JP9") (pin "1") (pinfunction "1_1") (pintype "passive"))
      (node (ref "R3") (pin "2") (pinfunction "2_2") (pintype "passive"))
    )
    (net (code "51") (name "Net-(JP9-Pad3)") (class "Default")
      (node (ref "JP9") (pin "3") (pinfunction "3_3") (pintype "passive"))
      (node (ref "R6") (pin "2") (pinfunction "2_2") (pintype "passive"))
    )
    (net (code "52") (name "Net-(Q3-B)") (class "Default")
      (node (ref "Q3") (pin "1") (pinfunction "B_1") (pintype "passive"))
      (node (ref "R23") (pin "1") (pinfunction "1_1") (pintype "passive"))
    )
    (net (code "53") (name "Net-(Q3-C)") (class "Default")
      (node (ref "Q3") (pin "3") (pinfunction "C_3") (pintype "passive"))
      (node (ref "R20") (pin "1") (pinfunction "1_1") (pintype "passive"))
    )
    (net (code "54") (name "Net-(Q4-B)") (class "Default")
      (node (ref "Q4") (pin "1") (pinfunction "B_1") (pintype "passive"))
      (node (ref "R24") (pin "1") (pinfunction "1_1") (pintype "passive"))
    )
    (net (code "55") (name "Net-(Q4-C)") (class "Default")
      (node (ref "Q4") (pin "3") (pinfunction "C_3") (pintype "passive"))
      (node (ref "R9") (pin "1") (pinfunction "1_1") (pintype "passive"))
    )
    (net (code "56") (name "Net-(Q5-B)") (class "Default")
      (node (ref "Q5") (pin "1") (pinfunction "B_1") (pintype "passive"))
      (node (ref "R25") (pin "1") (pinfunction "1_1") (pintype "passive"))
    )
    (net (code "57") (name "Net-(Q5-C)") (class "Default")
      (node (ref "Q5") (pin "3") (pinfunction "C_3") (pintype "passive"))
      (node (ref "R21") (pin "1") (pinfunction "1_1") (pintype "passive"))
    )
    (net (code "58") (name "Net-(Q6-B)") (class "Default")
      (node (ref "Q6") (pin "1") (pinfunction "B_1") (pintype "passive"))
      (node (ref "R26") (pin "1") (pinfunction "1_1") (pintype "passive"))
    )
    (net (code "59") (name "Net-(Q6-C)") (class "Default")
      (node (ref "Q6") (pin "3") (pinfunction "C_3") (pintype "passive"))
      (node (ref "R22") (pin "1") (pinfunction "1_1") (pintype "passive"))
    )
    (net (code "60") (name "Net-(Q7A-B)") (class "Default")
      (node (ref "Q7") (pin "2") (pinfunction "B_2") (pintype "passive"))
      (node (ref "Q7") (pin "5") (pinfunction "B_5") (pintype "passive"))
      (node (ref "Q7") (pin "6") (pinfunction "C_6") (pintype "passive"))
      (node (ref "R27") (pin "2") (pinfunction "2_2") (pintype "passive"))
    )
    (net (code "61") (name "Net-(Q7B-C)") (class "Default")
      (node (ref "Q7") (pin "3") (pinfunction "C_3") (pintype "passive"))
      (node (ref "Q8") (pin "1") (pinfunction "G_1") (pintype "bidirectional"))
      (node (ref "R28") (pin "2") (pinfunction "2_2") (pintype "passive"))
    )
    (net (code "62") (name "Net-(U2-PA00(XIN32{slash}SER1:0{slash}TC2:0))") (class "Default")
      (node (ref "C16") (pin "2") (pinfunction "2_2") (pintype "passive"))
      (node (ref "U2") (pin "1") (pinfunction "PA00(XIN32/SER1:0/TC2:0)_1") (pintype "bidirectional"))
      (node (ref "Y1") (pin "P$2") (pinfunction "2_P$2") (pintype "passive"))
    )
    (net (code "63") (name "Net-(U2-PA01(XOUT32{slash}SER1:1{slash}TC2:1))") (class "Default")
      (node (ref "C19") (pin "1") (pinfunction "1_1") (pintype "passive"))
      (node (ref "U2") (pin "2") (pinfunction "PA01(XOUT32/SER1:1/TC2:1)_2") (pintype "bidirectional"))
      (node (ref "Y1") (pin "P$1") (pinfunction "1_P$1") (pintype "passive"))
    )
    (net (code "64") (name "Net-(U2-VDDCORE)") (class "Default")
      (node (ref "C13") (pin "1") (pinfunction "1_1") (pintype "passive"))
      (node (ref "U2") (pin "43") (pinfunction "VDDCORE_43") (pintype "bidirectional"))
    )
    (net (code "65") (name "RX-I_HV") (class "Default")
      (node (ref "J5") (pin "2") (pinfunction "2_2") (pintype "passive"))
      (node (ref "Q2") (pin "3") (pinfunction "D_3") (pintype "bidirectional"))
      (node (ref "R13") (pin "1") (pinfunction "1_1") (pintype "passive"))
      (node (ref "TP7") (pin "1") (pinfunction "1_1") (pintype "bidirectional"))
    )
    (net (code "66") (name "RX-I_LV") (class "Default")
      (node (ref "Q2") (pin "2") (pinfunction "S_2") (pintype "bidirectional"))
      (node (ref "R11") (pin "1") (pinfunction "1_1") (pintype "passive"))
      (node (ref "U2") (pin "16") (pinfunction "PA11(AIN19/SER0:3+)_16") (pintype "bidirectional"))
    )
    (net (code "67") (name "SWCLK") (class "Default")
      (node (ref "J4") (pin "4") (pinfunction "SWDCLK_4") (pintype "bidirectional"))
      (node (ref "TP4") (pin "1") (pinfunction "1_1") (pintype "bidirectional"))
      (node (ref "U2") (pin "45") (pinfunction "PA30(SWCLK/SER1:2+)_45") (pintype "bidirectional"))
    )
    (net (code "68") (name "SWDIO") (class "Default")
      (node (ref "J4") (pin "2") (pinfunction "SWDIO_2") (pintype "bidirectional"))
      (node (ref "TP3") (pin "1") (pinfunction "1_1") (pintype "bidirectional"))
      (node (ref "U2") (pin "46") (pinfunction "PA31(SWDIO/SER1:3+)_46") (pintype "bidirectional"))
    )
    (net (code "69") (name "TX-O") (class "Default")
      (node (ref "J5") (pin "3") (pinfunction "3_3") (pintype "passive"))
      (node (ref "TP8") (pin "1") (pinfunction "1_1") (pintype "bidirectional"))
      (node (ref "U2") (pin "15") (pinfunction "PA10(AIN18/SER0:2+)_15") (pintype "bidirectional"))
    )
    (net (code "70") (name "VCC_CABLE") (class "Default")
      (node (ref "J5") (pin "1") (pinfunction "1_1") (pintype "passive"))
      (node (ref "Q7") (pin "1") (pinfunction "E_1") (pintype "passive"))
      (node (ref "Q8") (pin "3") (pinfunction "D_3") (pintype "bidirectional"))
    )
    (net (code "71") (name "V_USB") (class "Default")
      (node (ref "D9") (pin "A") (pinfunction "A_A") (pintype "passive"))
      (node (ref "F1") (pin "2") (pinfunction "2_2") (pintype "bidirectional"))
    )
    (net (code "72") (name "unconnected-(J4-SWO-Pad6)") (class "Default")
      (node (ref "J4") (pin "6") (pinfunction "SWO_6") (pintype "bidirectional"))
    )
    (net (code "73") (name "unconnected-(U2-PA27-Pad39)") (class "Default")
      (node (ref "U2") (pin "39") (pinfunction "PA27_39") (pintype "bidirectional"))
    )
    (net (code "74") (name "unconnected-(U2-PB03(AIN11{slash}SER5:1)-Pad48)") (class "Default")
      (node (ref "U2") (pin "48") (pinfunction "PB03(AIN11/SER5:1)_48") (pintype "bidirectional"))
    )
    (net (code "75") (name "unconnected-(U3-BP-Pad4)") (class "Default")
      (node (ref "U3") (pin "4") (pinfunction "BP_4") (pintype "input"))
    )
    (net (code "76") (name "unconnected-(U4-DIO2-Pad5)") (class "Default")
      (node (ref "U4") (pin "5") (pinfunction "DIO2_5") (pintype "bidirectional"))
    )
    (net (code "77") (name "unconnected-(U4-DIO3-Pad4)") (class "Default")
      (node (ref "U4") (pin "4") (pinfunction "DIO3_4") (pintype "bidirectional"))
    )
    (net (code "78") (name "unconnected-(U4-DIO4-Pad3)") (class "Default")
      (node (ref "U4") (pin "3") (pinfunction "DIO4_3") (pintype "bidirectional"))
    )
    (net (code "79") (name "unconnected-(U4-DIO5-Pad2)") (class "Default")
      (node (ref "U4") (pin "2") (pinfunction "DIO5_2") (pintype "bidirectional"))
    )
  )
)
